# main.net
KiCad netlist of a schematic drawn in Altium Designer
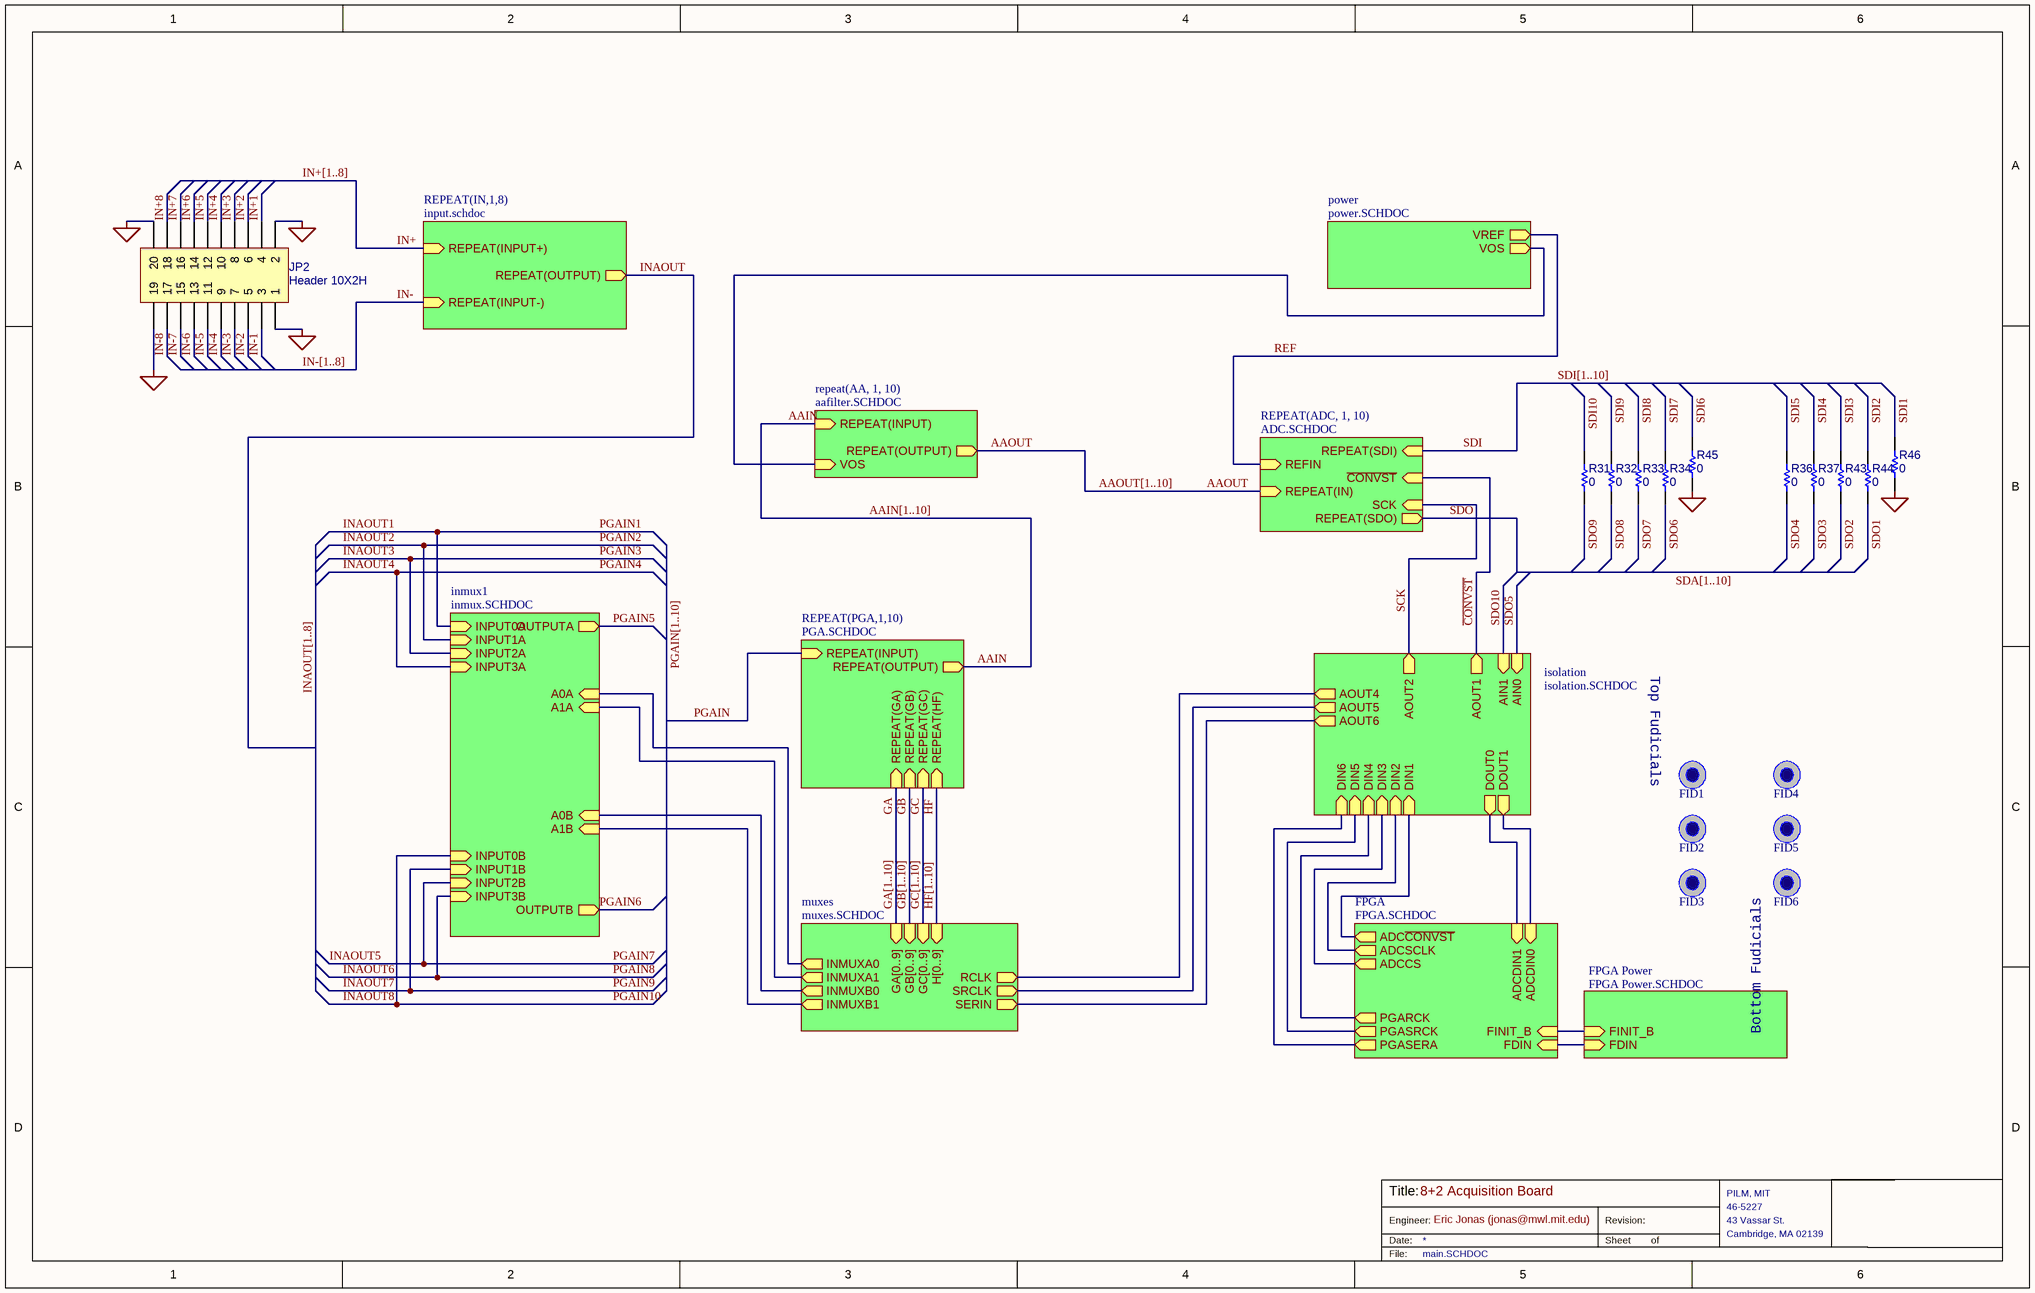
[diagram p0: main.SCHDOC]

(export (version "E")
  (design (tool "Eeschema 10.0.6"))
  (components
    (comp (ref "FID1")
      (value "FIDUCIAL")
      (footprint "FIDUCIAL")
      (description "Fiducial")
      (libsource (lib "parts") (part "FIDUCIAL"))
    )
    (comp (ref "FID2")
      (value "FIDUCIAL")
      (footprint "FIDUCIAL")
      (description "Fiducial")
      (libsource (lib "parts") (part "FIDUCIAL"))
    )
    (comp (ref "FID3")
      (value "FIDUCIAL")
      (footprint "FIDUCIAL")
      (description "Fiducial")
      (libsource (lib "parts") (part "FIDUCIAL"))
    )
    (comp (ref "FID4")
      (value "FIDUCIAL")
      (footprint "FIDUCIAL")
      (description "Fiducial")
      (libsource (lib "parts") (part "FIDUCIAL"))
    )
    (comp (ref "FID5")
      (value "FIDUCIAL")
      (footprint "FIDUCIAL")
      (description "Fiducial")
      (libsource (lib "parts") (part "FIDUCIAL"))
    )
    (comp (ref "FID6")
      (value "FIDUCIAL")
      (footprint "FIDUCIAL")
      (description "Fiducial")
      (libsource (lib "parts") (part "FIDUCIAL"))
    )
    (comp (ref "JP2")
      (value "Header 10X2H")
      (footprint "HDR2X10")
      (description "Header, 10-Pin, Dual row, Right Angle")
      (fields (field (name "MANUFACTURER") "Generic Components") (field (name "PUBLISHER") "Altium Limited"))
      (libsource (lib "Miscellaneous Connectors") (part "Header 10X2H"))
    )
    (comp (ref "R31")
      (value "0")
      (footprint "0603")
      (description "Standard Passive Resistor")
      (fields (field (name "Comment") "RESISTOR"))
      (libsource (lib "parts") (part "RESISTOR"))
    )
    (comp (ref "R32")
      (value "0")
      (footprint "0603")
      (description "Standard Passive Resistor")
      (fields (field (name "Comment") "RESISTOR"))
      (libsource (lib "parts") (part "RESISTOR"))
    )
    (comp (ref "R33")
      (value "0")
      (footprint "0603")
      (description "Standard Passive Resistor")
      (fields (field (name "Comment") "RESISTOR"))
      (libsource (lib "parts") (part "RESISTOR"))
    )
    (comp (ref "R34")
      (value "0")
      (footprint "0603")
      (description "Standard Passive Resistor")
      (fields (field (name "Comment") "RESISTOR"))
      (libsource (lib "parts") (part "RESISTOR"))
    )
    (comp (ref "R36")
      (value "0")
      (footprint "0603")
      (description "Standard Passive Resistor")
      (fields (field (name "Comment") "RESISTOR"))
      (libsource (lib "parts") (part "RESISTOR"))
    )
    (comp (ref "R37")
      (value "0")
      (footprint "0603")
      (description "Standard Passive Resistor")
      (fields (field (name "Comment") "RESISTOR"))
      (libsource (lib "parts") (part "RESISTOR"))
    )
    (comp (ref "R43")
      (value "0")
      (footprint "0603")
      (description "Standard Passive Resistor")
      (fields (field (name "Comment") "RESISTOR"))
      (libsource (lib "parts") (part "RESISTOR"))
    )
    (comp (ref "R44")
      (value "0")
      (footprint "0603")
      (description "Standard Passive Resistor")
      (fields (field (name "Comment") "RESISTOR"))
      (libsource (lib "parts") (part "RESISTOR"))
    )
    (comp (ref "R45")
      (value "0")
      (footprint "0603")
      (description "Standard Passive Resistor")
      (fields (field (name "Comment") "RESISTOR"))
      (libsource (lib "parts") (part "RESISTOR"))
    )
    (comp (ref "R46")
      (value "0")
      (footprint "0603")
      (description "Standard Passive Resistor")
      (fields (field (name "Comment") "RESISTOR"))
      (libsource (lib "parts") (part "RESISTOR"))
    )
  )
  (nets
    (net (code "93") (name "/IN+1") (class "Default")
      (node (ref "JP2") (pin "4") (pinfunction "4_4") (pintype "passive"))
    )
    (net (code "94") (name "/IN+2") (class "Default")
      (node (ref "JP2") (pin "6") (pinfunction "6_6") (pintype "passive"))
    )
    (net (code "95") (name "/IN+3") (class "Default")
      (node (ref "JP2") (pin "8") (pinfunction "8_8") (pintype "passive"))
    )
    (net (code "96") (name "/IN+4") (class "Default")
      (node (ref "JP2") (pin "10") (pinfunction "10_10") (pintype "passive"))
    )
    (net (code "97") (name "/IN+5") (class "Default")
      (node (ref "JP2") (pin "12") (pinfunction "12_12") (pintype "passive"))
    )
    (net (code "98") (name "/IN+6") (class "Default")
      (node (ref "JP2") (pin "14") (pinfunction "14_14") (pintype "passive"))
    )
    (net (code "99") (name "/IN+7") (class "Default")
      (node (ref "JP2") (pin "16") (pinfunction "16_16") (pintype "passive"))
    )
    (net (code "100") (name "/IN+8") (class "Default")
      (node (ref "JP2") (pin "18") (pinfunction "18_18") (pintype "passive"))
    )
    (net (code "103") (name "/IN-1") (class "Default")
      (node (ref "JP2") (pin "3") (pinfunction "3_3") (pintype "passive"))
    )
    (net (code "104") (name "/IN-2") (class "Default")
      (node (ref "JP2") (pin "5") (pinfunction "5_5") (pintype "passive"))
    )
    (net (code "105") (name "/IN-3") (class "Default")
      (node (ref "JP2") (pin "7") (pinfunction "7_7") (pintype "passive"))
    )
    (net (code "106") (name "/IN-4") (class "Default")
      (node (ref "JP2") (pin "9") (pinfunction "9_9") (pintype "passive"))
    )
    (net (code "107") (name "/IN-5") (class "Default")
      (node (ref "JP2") (pin "11") (pinfunction "11_11") (pintype "passive"))
    )
    (net (code "108") (name "/IN-6") (class "Default")
      (node (ref "JP2") (pin "13") (pinfunction "13_13") (pintype "passive"))
    )
    (net (code "109") (name "/IN-7") (class "Default")
      (node (ref "JP2") (pin "15") (pinfunction "15_15") (pintype "passive"))
    )
    (net (code "110") (name "/IN-8") (class "Default")
      (node (ref "JP2") (pin "17") (pinfunction "17_17") (pintype "passive"))
    )
    (net (code "138") (name "/SDI1") (class "Default") (node (ref "R46") (pin "2") (pintype "passive")))
    (net (code "139") (name "/SDI2") (class "Default") (node (ref "R44") (pin "2") (pintype "passive")))
    (net (code "140") (name "/SDI3") (class "Default") (node (ref "R43") (pin "2") (pintype "passive")))
    (net (code "141") (name "/SDI4") (class "Default") (node (ref "R37") (pin "2") (pintype "passive")))
    (net (code "142") (name "/SDI5") (class "Default") (node (ref "R36") (pin "2") (pintype "passive")))
    (net (code "143") (name "/SDI6") (class "Default") (node (ref "R45") (pin "2") (pintype "passive")))
    (net (code "144") (name "/SDI7") (class "Default") (node (ref "R34") (pin "2") (pintype "passive")))
    (net (code "145") (name "/SDI8") (class "Default") (node (ref "R33") (pin "2") (pintype "passive")))
    (net (code "146") (name "/SDI9") (class "Default") (node (ref "R32") (pin "2") (pintype "passive")))
    (net (code "147") (name "/SDI10") (class "Default") (node (ref "R31") (pin "2") (pintype "passive")))
    (net (code "150") (name "/SDO1") (class "Default") (node (ref "R44") (pin "1") (pintype "passive")))
    (net (code "151") (name "/SDO2") (class "Default") (node (ref "R43") (pin "1") (pintype "passive")))
    (net (code "152") (name "/SDO3") (class "Default") (node (ref "R37") (pin "1") (pintype "passive")))
    (net (code "153") (name "/SDO4") (class "Default") (node (ref "R36") (pin "1") (pintype "passive")))
    (net (code "155") (name "/SDO6") (class "Default") (node (ref "R34") (pin "1") (pintype "passive")))
    (net (code "156") (name "/SDO7") (class "Default") (node (ref "R33") (pin "1") (pintype "passive")))
    (net (code "157") (name "/SDO8") (class "Default") (node (ref "R32") (pin "1") (pintype "passive")))
    (net (code "158") (name "/SDO9") (class "Default") (node (ref "R31") (pin "1") (pintype "passive")))
    (net (code "162") (name "AGND") (class "Default")
      (node (ref "JP2") (pin "1") (pinfunction "1_1") (pintype "passive"))
      (node (ref "JP2") (pin "19") (pinfunction "19_19") (pintype "passive"))
      (node (ref "JP2") (pin "2") (pinfunction "2_2") (pintype "passive"))
      (node (ref "JP2") (pin "20") (pinfunction "20_20") (pintype "passive"))
      (node (ref "R45") (pin "1") (pintype "passive"))
      (node (ref "R46") (pin "1") (pintype "passive"))
    )
  )
)
